# mika.net
KiCad netlist of a schematic drawn in EAGLE
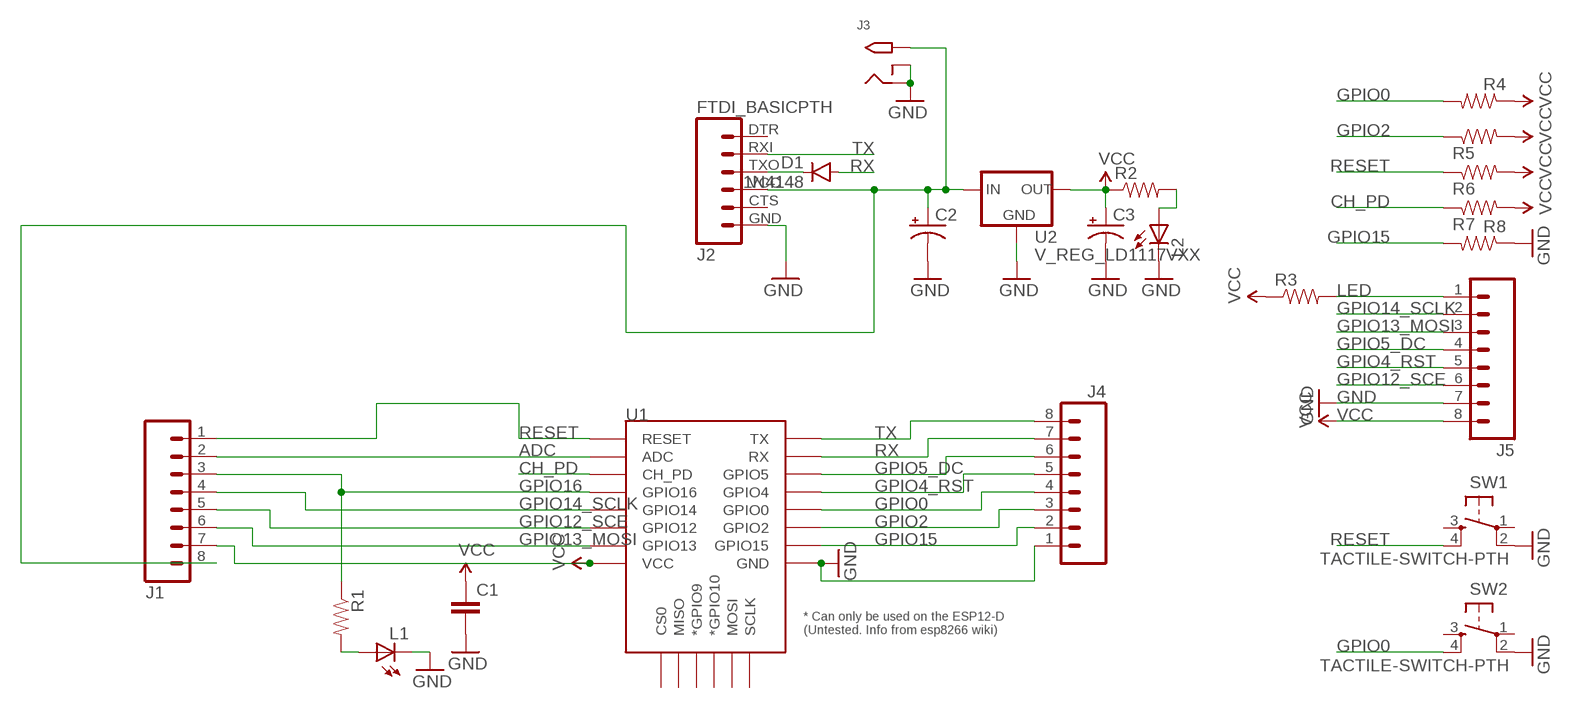
[diagram p0: schematic, sheet 1]

(export (version "E")
  (design (tool "Eeschema 10.0.6"))
  (components
    (comp (ref "C1")
      (value "CAPKIT")
      (footprint "eagle-import:CAP-PTH-SMALL-KIT")
      (libsource (lib "eagle-import") (part "CAPKIT"))
    )
    (comp (ref "C2")
      (value "CAP_POLPTH2")
      (footprint "eagle-import:CPOL-RADIAL-10UF-25V")
      (libsource (lib "eagle-import") (part "CAP_POLPTH2"))
    )
    (comp (ref "C3")
      (value "CAP_POLPTH2")
      (footprint "eagle-import:CPOL-RADIAL-10UF-25V")
      (libsource (lib "eagle-import") (part "CAP_POLPTH2"))
    )
    (comp (ref "D1")
      (value "1N4148")
      (footprint "eagle-import:DIODE-1N4148")
      (libsource (lib "eagle-import") (part "DIODE1N4148"))
    )
    (comp (ref "J1")
      (value "M083.5MM-8")
      (footprint "eagle-import:SCREWTERMINAL-3.5MM-8")
      (libsource (lib "eagle-import") (part "M083.5MM-8"))
    )
    (comp (ref "J2")
      (value "FTDI_BASICPTH")
      (footprint "eagle-import:FTDI_BASIC")
      (libsource (lib "eagle-import") (part "FTDI_BASICPTH"))
    )
    (comp (ref "J3")
      (value "2.1MMJACKTHM")
      (footprint "eagle-import:PJ-102A")
      (libsource (lib "eagle-import") (part "2.1MMJACKTHM"))
    )
    (comp (ref "J4")
      (value "M083.5MM-8")
      (footprint "eagle-import:SCREWTERMINAL-3.5MM-8")
      (libsource (lib "eagle-import") (part "M083.5MM-8"))
    )
    (comp (ref "J5")
      (value "M08")
      (footprint "eagle-import:1X08_ROUND")
      (libsource (lib "eagle-import") (part "M08"))
    )
    (comp (ref "L1")
      (value "LED5MM")
      (footprint "eagle-import:LED5MM")
      (libsource (lib "eagle-import") (part "LED5MM"))
    )
    (comp (ref "L2")
      (value "LED5MM")
      (footprint "eagle-import:LED5MM")
      (libsource (lib "eagle-import") (part "LED5MM"))
    )
    (comp (ref "R1")
      (value "RESISTORKIT")
      (footprint "eagle-import:AXIAL-0.3-KIT")
      (libsource (lib "eagle-import") (part "RESISTORKIT"))
    )
    (comp (ref "R2")
      (value "RESISTORKIT")
      (footprint "eagle-import:AXIAL-0.3-KIT")
      (libsource (lib "eagle-import") (part "RESISTORKIT"))
    )
    (comp (ref "R3")
      (value "RESISTORKIT")
      (footprint "eagle-import:AXIAL-0.3-KIT")
      (libsource (lib "eagle-import") (part "RESISTORKIT"))
    )
    (comp (ref "R4")
      (value "RESISTORKIT")
      (footprint "eagle-import:AXIAL-0.3-KIT")
      (libsource (lib "eagle-import") (part "RESISTORKIT"))
    )
    (comp (ref "R5")
      (value "RESISTORKIT")
      (footprint "eagle-import:AXIAL-0.3-KIT")
      (libsource (lib "eagle-import") (part "RESISTORKIT"))
    )
    (comp (ref "R6")
      (value "RESISTORKIT")
      (footprint "eagle-import:AXIAL-0.3-KIT")
      (libsource (lib "eagle-import") (part "RESISTORKIT"))
    )
    (comp (ref "R7")
      (value "RESISTORKIT")
      (footprint "eagle-import:AXIAL-0.3-KIT")
      (libsource (lib "eagle-import") (part "RESISTORKIT"))
    )
    (comp (ref "R8")
      (value "RESISTORKIT")
      (footprint "eagle-import:AXIAL-0.3-KIT")
      (libsource (lib "eagle-import") (part "RESISTORKIT"))
    )
    (comp (ref "SW1")
      (value "TACTILE-SWITCH-PTH")
      (footprint "eagle-import:TAC-SWITCH-PTH")
      (libsource (lib "eagle-import") (part "TACTILE-SWITCH-PTH"))
    )
    (comp (ref "SW2")
      (value "TACTILE-SWITCH-PTH")
      (footprint "eagle-import:TAC-SWITCH-PTH")
      (libsource (lib "eagle-import") (part "TACTILE-SWITCH-PTH"))
    )
    (comp (ref "U1")
      (value "ESP12ESMD")
      (footprint "eagle-import:ESP12E-SMD")
      (libsource (lib "eagle-import") (part "ESP12ESMD"))
    )
    (comp (ref "U2")
      (value "V_REG_LD1117VXX")
      (footprint "eagle-import:78XXL")
      (libsource (lib "eagle-import") (part "V_REG_LD1117VXX"))
    )
  )
  (nets
    (net (code "1") (name "/ADC") (class "Default")
      (node (ref "J1") (pin "2") (pinfunction "2_2") (pintype "passive"))
      (node (ref "U1") (pin "ADC") (pinfunction "ADC_ADC") (pintype "bidirectional"))
    )
    (net (code "2") (name "/CH_PD") (class "Default")
      (node (ref "R7") (pin "P$1") (pinfunction "1_P$1") (pintype "passive"))
      (node (ref "U1") (pin "CH_PD") (pinfunction "CH_PD_CH_PD") (pintype "bidirectional"))
    )
    (net (code "3") (name "/GPIO0") (class "Default")
      (node (ref "J4") (pin "4") (pinfunction "4_4") (pintype "passive"))
      (node (ref "R4") (pin "P$2") (pinfunction "2_P$2") (pintype "passive"))
      (node (ref "SW2") (pin "4") (pinfunction "4_4") (pintype "passive"))
      (node (ref "U1") (pin "GPIO0") (pinfunction "GPIO0_GPIO0") (pintype "bidirectional"))
    )
    (net (code "4") (name "/GPIO2") (class "Default")
      (node (ref "J4") (pin "3") (pinfunction "3_3") (pintype "passive"))
      (node (ref "R5") (pin "P$1") (pinfunction "1_P$1") (pintype "passive"))
      (node (ref "U1") (pin "GPIO2") (pinfunction "GPIO2_GPIO2") (pintype "bidirectional"))
    )
    (net (code "5") (name "/GPIO4_RST") (class "Default")
      (node (ref "J4") (pin "5") (pinfunction "5_5") (pintype "passive"))
      (node (ref "J5") (pin "5") (pinfunction "5_5") (pintype "passive"))
      (node (ref "U1") (pin "GPIO4") (pinfunction "GPIO4_GPIO4") (pintype "bidirectional"))
    )
    (net (code "6") (name "/GPIO5_DC") (class "Default")
      (node (ref "J4") (pin "6") (pinfunction "6_6") (pintype "passive"))
      (node (ref "J5") (pin "4") (pinfunction "4_4") (pintype "passive"))
      (node (ref "U1") (pin "GPIO5") (pinfunction "GPIO5_GPIO5") (pintype "bidirectional"))
    )
    (net (code "7") (name "/GPIO12_SCE") (class "Default")
      (node (ref "J1") (pin "5") (pinfunction "5_5") (pintype "passive"))
      (node (ref "J5") (pin "6") (pinfunction "6_6") (pintype "passive"))
      (node (ref "U1") (pin "GPIO12") (pinfunction "GPIO12_GPIO12") (pintype "bidirectional"))
    )
    (net (code "8") (name "/GPIO13_MOSI") (class "Default")
      (node (ref "J1") (pin "6") (pinfunction "6_6") (pintype "passive"))
      (node (ref "J5") (pin "3") (pinfunction "3_3") (pintype "passive"))
      (node (ref "U1") (pin "GPIO13") (pinfunction "GPIO13_GPIO13") (pintype "bidirectional"))
    )
    (net (code "9") (name "/GPIO14_SCLK") (class "Default")
      (node (ref "J1") (pin "4") (pinfunction "4_4") (pintype "passive"))
      (node (ref "J5") (pin "2") (pinfunction "2_2") (pintype "passive"))
      (node (ref "U1") (pin "GPIO14") (pinfunction "GPIO14_GPIO14") (pintype "bidirectional"))
    )
    (net (code "10") (name "/GPIO15") (class "Default")
      (node (ref "J4") (pin "2") (pinfunction "2_2") (pintype "passive"))
      (node (ref "R8") (pin "P$2") (pinfunction "2_P$2") (pintype "passive"))
      (node (ref "U1") (pin "GPIO15") (pinfunction "GPIO15_GPIO15") (pintype "bidirectional"))
    )
    (net (code "11") (name "/GPIO16") (class "Default")
      (node (ref "J1") (pin "3") (pinfunction "3_3") (pintype "passive"))
      (node (ref "R1") (pin "P$1") (pinfunction "1_P$1") (pintype "passive"))
      (node (ref "U1") (pin "GPIO16") (pinfunction "GPIO16_GPIO16") (pintype "bidirectional"))
    )
    (net (code "12") (name "/LED") (class "Default")
      (node (ref "J5") (pin "1") (pinfunction "1_1") (pintype "passive"))
      (node (ref "R3") (pin "P$2") (pinfunction "2_P$2") (pintype "passive"))
    )
    (net (code "13") (name "/RESET") (class "Default")
      (node (ref "J1") (pin "1") (pinfunction "1_1") (pintype "passive"))
      (node (ref "R6") (pin "P$1") (pinfunction "1_P$1") (pintype "passive"))
      (node (ref "SW1") (pin "4") (pinfunction "4_4") (pintype "passive"))
      (node (ref "U1") (pin "RESET") (pinfunction "RESET_RESET") (pintype "bidirectional"))
    )
    (net (code "14") (name "/RX") (class "Default")
      (node (ref "D1") (pin "A") (pinfunction "A_A") (pintype "passive"))
      (node (ref "J4") (pin "7") (pinfunction "7_7") (pintype "passive"))
      (node (ref "U1") (pin "RXD0") (pinfunction "RX_RXD0") (pintype "bidirectional"))
    )
    (net (code "15") (name "/TX") (class "Default")
      (node (ref "J2") (pin "RXI") (pinfunction "2_RXI") (pintype "passive"))
      (node (ref "J4") (pin "8") (pinfunction "8_8") (pintype "passive"))
      (node (ref "U1") (pin "TXD0") (pinfunction "TX_TXD0") (pintype "bidirectional"))
    )
    (net (code "16") (name "GND") (class "Default")
      (node (ref "C1") (pin "2") (pinfunction "2_2") (pintype "passive"))
      (node (ref "C2") (pin "2") (pinfunction "-_2") (pintype "passive"))
      (node (ref "C3") (pin "2") (pinfunction "-_2") (pintype "passive"))
      (node (ref "J2") (pin "GND") (pinfunction "6_GND") (pintype "passive"))
      (node (ref "J3") (pin "RING") (pinfunction "RING_RING") (pintype "bidirectional"))
      (node (ref "J3") (pin "RING_SW") (pinfunction "RING_SW_RING_SW") (pintype "bidirectional"))
      (node (ref "J4") (pin "1") (pinfunction "1_1") (pintype "passive"))
      (node (ref "J5") (pin "7") (pinfunction "7_7") (pintype "passive"))
      (node (ref "L1") (pin "K") (pinfunction "C_K") (pintype "passive"))
      (node (ref "L2") (pin "K") (pinfunction "C_K") (pintype "passive"))
      (node (ref "R8") (pin "P$1") (pinfunction "1_P$1") (pintype "passive"))
      (node (ref "SW1") (pin "2") (pinfunction "2_2") (pintype "passive"))
      (node (ref "SW2") (pin "2") (pinfunction "2_2") (pintype "passive"))
      (node (ref "U1") (pin "GND") (pinfunction "GND_GND") (pintype "bidirectional"))
      (node (ref "U2") (pin "GND") (pinfunction "GND_GND") (pintype "input"))
    )
    (net (code "17") (name "Net-(C2-+)") (class "Default")
      (node (ref "C2") (pin "1") (pinfunction "+_1") (pintype "passive"))
      (node (ref "J1") (pin "8") (pinfunction "8_8") (pintype "passive"))
      (node (ref "J2") (pin "VCC") (pinfunction "4_VCC") (pintype "passive"))
      (node (ref "J3") (pin "TIP") (pinfunction "TIP_TIP") (pintype "bidirectional"))
      (node (ref "U2") (pin "IN") (pinfunction "IN_IN") (pintype "input"))
    )
    (net (code "18") (name "Net-(J2-3)") (class "Default")
      (node (ref "D1") (pin "C") (pinfunction "C_C") (pintype "passive"))
      (node (ref "J2") (pin "TXO") (pinfunction "3_TXO") (pintype "passive"))
    )
    (net (code "19") (name "Net-(R1-2)") (class "Default")
      (node (ref "L1") (pin "A") (pinfunction "A_A") (pintype "passive"))
      (node (ref "R1") (pin "P$2") (pinfunction "2_P$2") (pintype "passive"))
    )
    (net (code "20") (name "Net-(R2-2)") (class "Default")
      (node (ref "L2") (pin "A") (pinfunction "A_A") (pintype "passive"))
      (node (ref "R2") (pin "P$2") (pinfunction "2_P$2") (pintype "passive"))
    )
    (net (code "21") (name "VCC") (class "Default")
      (node (ref "C1") (pin "1") (pinfunction "1_1") (pintype "passive"))
      (node (ref "C3") (pin "1") (pinfunction "+_1") (pintype "passive"))
      (node (ref "J1") (pin "7") (pinfunction "7_7") (pintype "passive"))
      (node (ref "J5") (pin "8") (pinfunction "8_8") (pintype "passive"))
      (node (ref "R2") (pin "P$1") (pinfunction "1_P$1") (pintype "passive"))
      (node (ref "R3") (pin "P$1") (pinfunction "1_P$1") (pintype "passive"))
      (node (ref "R4") (pin "P$1") (pinfunction "1_P$1") (pintype "passive"))
      (node (ref "R5") (pin "P$2") (pinfunction "2_P$2") (pintype "passive"))
      (node (ref "R6") (pin "P$2") (pinfunction "2_P$2") (pintype "passive"))
      (node (ref "R7") (pin "P$2") (pinfunction "2_P$2") (pintype "passive"))
      (node (ref "U1") (pin "VCC") (pinfunction "VCC_VCC") (pintype "bidirectional"))
      (node (ref "U2") (pin "OUT") (pinfunction "OUT_OUT") (pintype "passive"))
    )
    (net (code "22") (name "unconnected-(J2-1-PadDTR)") (class "Default")
      (node (ref "J2") (pin "DTR") (pinfunction "1_DTR") (pintype "passive"))
    )
    (net (code "23") (name "unconnected-(J2-5-PadCTS)") (class "Default")
      (node (ref "J2") (pin "CTS") (pinfunction "5_CTS") (pintype "passive"))
    )
    (net (code "24") (name "unconnected-(SW1-Pad1)") (class "Default")
      (node (ref "SW1") (pin "1") (pinfunction "1_1") (pintype "passive"))
    )
    (net (code "25") (name "unconnected-(SW1-Pad3)") (class "Default")
      (node (ref "SW1") (pin "3") (pinfunction "3_3") (pintype "passive"))
    )
    (net (code "26") (name "unconnected-(SW2-Pad1)") (class "Default")
      (node (ref "SW2") (pin "1") (pinfunction "1_1") (pintype "passive"))
    )
    (net (code "27") (name "unconnected-(SW2-Pad3)") (class "Default")
      (node (ref "SW2") (pin "3") (pinfunction "3_3") (pintype "passive"))
    )
    (net (code "28") (name "unconnected-(U1-*GPIO9-PadGPIO9)") (class "Default")
      (node (ref "U1") (pin "GPIO9") (pinfunction "*GPIO9_GPIO9") (pintype "bidirectional"))
    )
    (net (code "29") (name "unconnected-(U1-*GPIO10-PadGPIO10)") (class "Default")
      (node (ref "U1") (pin "GPIO10") (pinfunction "*GPIO10_GPIO10") (pintype "bidirectional"))
    )
    (net (code "30") (name "unconnected-(U1-PadCS0)") (class "Default")
      (node (ref "U1") (pin "CS0") (pinfunction "CS0_CS0") (pintype "bidirectional"))
    )
    (net (code "31") (name "unconnected-(U1-PadMISO)") (class "Default")
      (node (ref "U1") (pin "MISO") (pinfunction "MISO_MISO") (pintype "bidirectional"))
    )
    (net (code "32") (name "unconnected-(U1-PadMOSI)") (class "Default")
      (node (ref "U1") (pin "MOSI") (pinfunction "MOSI_MOSI") (pintype "bidirectional"))
    )
    (net (code "33") (name "unconnected-(U1-PadSCLK)") (class "Default")
      (node (ref "U1") (pin "SCLK") (pinfunction "SCLK_SCLK") (pintype "bidirectional"))
    )
  )
)
